# Gravador.net
KiCad netlist of a schematic drawn in EAGLE
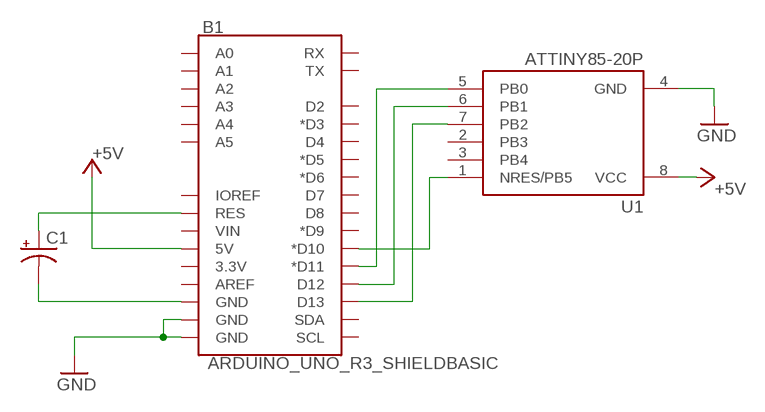
[diagram p0: schematic, sheet 1]

(export (version "E")
  (design (tool "Eeschema 10.0.6"))
  (components
    (comp (ref "B1")
      (value "ARDUINO_UNO_R3_SHIELDBASIC")
      (footprint "eagle-import:UNO_R3_SHIELD")
      (libsource (lib "eagle-import") (part "ARDUINO_UNO_R3_SHIELDBASIC"))
    )
    (comp (ref "C1")
      (value "CPOL-USE2.5-5")
      (footprint "eagle-import:E2,5-5")
      (libsource (lib "eagle-import") (part "CPOL-USE2.5-5"))
    )
    (comp (ref "U1")
      (value "ATTINY85-20P")
      (footprint "eagle-import:PDIP08_300MIL")
      (libsource (lib "eagle-import") (part "ATTINY85P-20"))
    )
  )
  (nets
    (net (code "1") (name "+5V") (class "Default")
      (node (ref "B1") (pin "5V") (pinfunction "5V_5V") (pintype "bidirectional"))
      (node (ref "U1") (pin "8") (pinfunction "VCC_8") (pintype "power_in"))
    )
    (net (code "2") (name "GND") (class "Default")
      (node (ref "B1") (pin "GND@0") (pinfunction "GND_GND@0") (pintype "bidirectional"))
      (node (ref "B1") (pin "GND@1") (pinfunction "GND_GND@1") (pintype "bidirectional"))
      (node (ref "U1") (pin "4") (pinfunction "GND_4") (pintype "power_in"))
    )
    (net (code "3") (name "Net-(B1-*D10)") (class "Default")
      (node (ref "B1") (pin "D10") (pinfunction "*D10_D10") (pintype "bidirectional"))
      (node (ref "U1") (pin "1") (pinfunction "NRES/PB5_1") (pintype "bidirectional"))
    )
    (net (code "4") (name "Net-(B1-*D11)") (class "Default")
      (node (ref "B1") (pin "D11") (pinfunction "*D11_D11") (pintype "bidirectional"))
      (node (ref "U1") (pin "5") (pinfunction "PB0_5") (pintype "bidirectional"))
    )
    (net (code "5") (name "Net-(B1-GND-PadGND@2)") (class "Default")
      (node (ref "B1") (pin "GND@2") (pinfunction "GND_GND@2") (pintype "bidirectional"))
      (node (ref "C1") (pin "-") (pinfunction "-_-") (pintype "passive"))
    )
    (net (code "6") (name "Net-(B1-PadRES)") (class "Default")
      (node (ref "B1") (pin "RES") (pinfunction "RES_RES") (pintype "bidirectional"))
      (node (ref "C1") (pin "+") (pinfunction "+_+") (pintype "passive"))
    )
    (net (code "7") (name "Net-(U1-PB1)") (class "Default")
      (node (ref "B1") (pin "D12") (pinfunction "D12_D12") (pintype "bidirectional"))
      (node (ref "U1") (pin "6") (pinfunction "PB1_6") (pintype "bidirectional"))
    )
    (net (code "8") (name "Net-(U1-PB2)") (class "Default")
      (node (ref "B1") (pin "D13") (pinfunction "D13_D13") (pintype "bidirectional"))
      (node (ref "U1") (pin "7") (pinfunction "PB2_7") (pintype "bidirectional"))
    )
    (net (code "9") (name "unconnected-(B1-*D3-PadD3)") (class "Default")
      (node (ref "B1") (pin "D3") (pinfunction "*D3_D3") (pintype "bidirectional"))
    )
    (net (code "10") (name "unconnected-(B1-*D5-PadD5)") (class "Default")
      (node (ref "B1") (pin "D5") (pinfunction "*D5_D5") (pintype "bidirectional"))
    )
    (net (code "11") (name "unconnected-(B1-*D6-PadD6)") (class "Default")
      (node (ref "B1") (pin "D6") (pinfunction "*D6_D6") (pintype "bidirectional"))
    )
    (net (code "12") (name "unconnected-(B1-*D9-PadD9)") (class "Default")
      (node (ref "B1") (pin "D9") (pinfunction "*D9_D9") (pintype "bidirectional"))
    )
    (net (code "13") (name "unconnected-(B1-Pad3.3V)") (class "Default")
      (node (ref "B1") (pin "3.3V") (pinfunction "3.3V_3.3V") (pintype "bidirectional"))
    )
    (net (code "14") (name "unconnected-(B1-PadA0)") (class "Default")
      (node (ref "B1") (pin "A0") (pinfunction "A0_A0") (pintype "bidirectional"))
    )
    (net (code "15") (name "unconnected-(B1-PadA1)") (class "Default")
      (node (ref "B1") (pin "A1") (pinfunction "A1_A1") (pintype "bidirectional"))
    )
    (net (code "16") (name "unconnected-(B1-PadA2)") (class "Default")
      (node (ref "B1") (pin "A2") (pinfunction "A2_A2") (pintype "bidirectional"))
    )
    (net (code "17") (name "unconnected-(B1-PadA3)") (class "Default")
      (node (ref "B1") (pin "A3") (pinfunction "A3_A3") (pintype "bidirectional"))
    )
    (net (code "18") (name "unconnected-(B1-PadA4)") (class "Default")
      (node (ref "B1") (pin "A4") (pinfunction "A4_A4") (pintype "bidirectional"))
    )
    (net (code "19") (name "unconnected-(B1-PadA5)") (class "Default")
      (node (ref "B1") (pin "A5") (pinfunction "A5_A5") (pintype "bidirectional"))
    )
    (net (code "20") (name "unconnected-(B1-PadAREF)") (class "Default")
      (node (ref "B1") (pin "AREF") (pinfunction "AREF_AREF") (pintype "bidirectional"))
    )
    (net (code "21") (name "unconnected-(B1-PadD2)") (class "Default")
      (node (ref "B1") (pin "D2") (pinfunction "D2_D2") (pintype "bidirectional"))
    )
    (net (code "22") (name "unconnected-(B1-PadD4)") (class "Default")
      (node (ref "B1") (pin "D4") (pinfunction "D4_D4") (pintype "bidirectional"))
    )
    (net (code "23") (name "unconnected-(B1-PadD7)") (class "Default")
      (node (ref "B1") (pin "D7") (pinfunction "D7_D7") (pintype "bidirectional"))
    )
    (net (code "24") (name "unconnected-(B1-PadD8)") (class "Default")
      (node (ref "B1") (pin "D8") (pinfunction "D8_D8") (pintype "bidirectional"))
    )
    (net (code "25") (name "unconnected-(B1-PadIOREF)") (class "Default")
      (node (ref "B1") (pin "IOREF") (pinfunction "IOREF_IOREF") (pintype "bidirectional"))
    )
    (net (code "26") (name "unconnected-(B1-PadRX)") (class "Default")
      (node (ref "B1") (pin "RX") (pinfunction "RX_RX") (pintype "bidirectional"))
    )
    (net (code "27") (name "unconnected-(B1-PadSCL)") (class "Default")
      (node (ref "B1") (pin "SCL") (pinfunction "SCL_SCL") (pintype "bidirectional"))
    )
    (net (code "28") (name "unconnected-(B1-PadSDA)") (class "Default")
      (node (ref "B1") (pin "SDA") (pinfunction "SDA_SDA") (pintype "bidirectional"))
    )
    (net (code "29") (name "unconnected-(B1-PadTX)") (class "Default")
      (node (ref "B1") (pin "TX") (pinfunction "TX_TX") (pintype "bidirectional"))
    )
    (net (code "30") (name "unconnected-(B1-PadVIN)") (class "Default")
      (node (ref "B1") (pin "VIN") (pinfunction "VIN_VIN") (pintype "bidirectional"))
    )
    (net (code "31") (name "unconnected-(U1-PB3-Pad2)") (class "Default")
      (node (ref "U1") (pin "2") (pinfunction "PB3_2") (pintype "bidirectional"))
    )
    (net (code "32") (name "unconnected-(U1-PB4-Pad3)") (class "Default")
      (node (ref "U1") (pin "3") (pinfunction "PB4_3") (pintype "bidirectional"))
    )
  )
)
